# H_bridge.net
KiCad netlist of a schematic drawn in Altium Designer
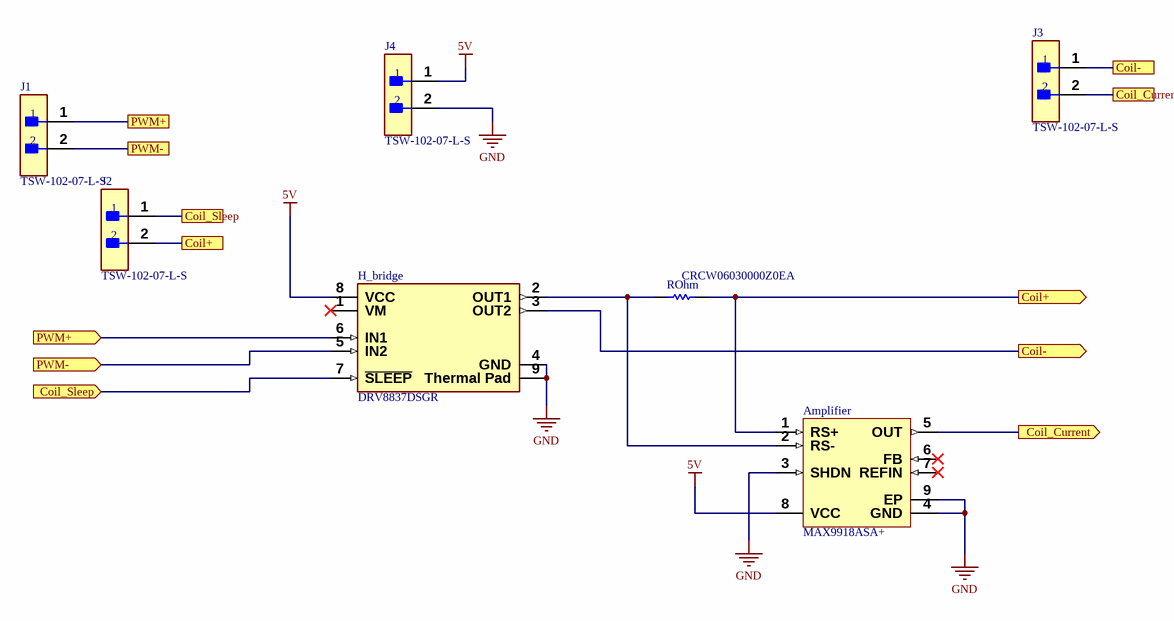
[diagram p0: H_bridge.SchDoc]

(export (version "E")
  (design (tool "Eeschema 10.0.6"))
  (components
    (comp (ref "Amplifier")
      (value "MAX9918ASA+")
      (footprint "MAXM-S8E+14_L")
      (libsource (lib "Altium Content Vault") (part "MAX99XX-S8E+14"))
    )
    (comp (ref "H_bridge")
      (value "DRV8837DSGR")
      (footprint "FP-DSG0008A-MFG")
      (description "IC MOTOR DRIVER PAR 8WSON")
      (fields
        (field (name "MANUFACTURER") "Texas Instruments")
        (field (name "OCTOPART") "https://octopart.com/drv8837dsgr-texas+instruments-23786726")
      )
      (libsource (lib "Altium Content Vault") (part "0edabe62f55b79d65ef7cb8a22a7164"))
    )
    (comp (ref "J1")
      (value "TSW-102-07-L-S")
      (footprint "FP-TSW-102-07-L-S-MFG")
      (description "CONN HEADER VERT 2POS 2.54MM")
      (libsource (lib "Altium Content Vault") (part "3bc925449376181038e59eaffc5286c"))
    )
    (comp (ref "J2")
      (value "TSW-102-07-L-S")
      (footprint "FP-TSW-102-07-L-S-MFG")
      (description "CONN HEADER VERT 2POS 2.54MM")
      (libsource (lib "Altium Content Vault") (part "3bc925449376181038e59eaffc5286c"))
    )
    (comp (ref "J3")
      (value "TSW-102-07-L-S")
      (footprint "FP-TSW-102-07-L-S-MFG")
      (description "CONN HEADER VERT 2POS 2.54MM")
      (libsource (lib "Altium Content Vault") (part "3bc925449376181038e59eaffc5286c"))
    )
    (comp (ref "J4")
      (value "TSW-102-07-L-S")
      (footprint "FP-TSW-102-07-L-S-MFG")
      (description "CONN HEADER VERT 2POS 2.54MM")
      (libsource (lib "Altium Content Vault") (part "3bc925449376181038e59eaffc5286c"))
    )
    (comp (ref "ROhm")
      (value "CRCW06030000Z0EA")
      (footprint "RESC1609X50X30NL8T20")
      (description "Chip Resistor, 0 Ohm, Jumper, 100 mW, -55 to 155 degC, 0603 (1608 Metric), RoHS, Tape and Reel")
      (fields (field (name "MANUFACTURER") "Vishay Semiconductor"))
      (libsource (lib "Altium Content Vault") (part "RES-2"))
    )
  )
  (nets
    (net (code "1") (name "/Coil+") (class "Default")
      (node (ref "Amplifier") (pin "1") (pinfunction "RS+_1") (pintype "input"))
      (node (ref "J2") (pin "2") (pinfunction "2_2") (pintype "passive"))
      (node (ref "ROhm") (pin "2") (pinfunction "2_2") (pintype "passive"))
    )
    (net (code "2") (name "/Coil-") (class "Default")
      (node (ref "H_bridge") (pin "3") (pinfunction "OUT2_3") (pintype "output"))
      (node (ref "J3") (pin "1") (pinfunction "1_1") (pintype "passive"))
    )
    (net (code "3") (name "/Coil_Current") (class "Default")
      (node (ref "Amplifier") (pin "5") (pinfunction "OUT_5") (pintype "output"))
      (node (ref "J3") (pin "2") (pinfunction "2_2") (pintype "passive"))
    )
    (net (code "4") (name "/Coil_Sleep") (class "Default")
      (node (ref "H_bridge") (pin "7") (pinfunction "~{SLEEP}_7") (pintype "input"))
      (node (ref "J2") (pin "1") (pinfunction "1_1") (pintype "passive"))
    )
    (net (code "5") (name "/PWM+") (class "Default")
      (node (ref "H_bridge") (pin "6") (pinfunction "IN1_6") (pintype "input"))
      (node (ref "J1") (pin "1") (pinfunction "1_1") (pintype "passive"))
    )
    (net (code "6") (name "/PWM-") (class "Default")
      (node (ref "H_bridge") (pin "5") (pinfunction "IN2_5") (pintype "input"))
      (node (ref "J1") (pin "2") (pinfunction "2_2") (pintype "passive"))
    )
    (net (code "7") (name "5V") (class "Default")
      (node (ref "Amplifier") (pin "8") (pinfunction "VCC_8") (pintype "power_in"))
      (node (ref "H_bridge") (pin "8") (pinfunction "VCC_8") (pintype "power_in"))
      (node (ref "J4") (pin "1") (pinfunction "1_1") (pintype "passive"))
    )
    (net (code "8") (name "GND") (class "Default")
      (node (ref "Amplifier") (pin "3") (pinfunction "SHDN_3") (pintype "input"))
      (node (ref "Amplifier") (pin "4") (pinfunction "GND_4") (pintype "power_in"))
      (node (ref "Amplifier") (pin "9") (pinfunction "EP_9") (pintype "power_in"))
      (node (ref "H_bridge") (pin "4") (pinfunction "GND_4") (pintype "power_in"))
      (node (ref "H_bridge") (pin "9") (pinfunction "Thermal_Pad_9") (pintype "power_in"))
      (node (ref "J4") (pin "2") (pinfunction "2_2") (pintype "passive"))
    )
    (net (code "9") (name "Net-(Amplifier-RS-)") (class "Default")
      (node (ref "Amplifier") (pin "2") (pinfunction "RS-_2") (pintype "input"))
      (node (ref "H_bridge") (pin "2") (pinfunction "OUT1_2") (pintype "output"))
      (node (ref "ROhm") (pin "1") (pinfunction "1_1") (pintype "passive"))
    )
    (net (code "10") (name "unconnected-(Amplifier-FB-Pad6)") (class "Default")
      (node (ref "Amplifier") (pin "6") (pinfunction "FB_6") (pintype "input+no_connect"))
    )
    (net (code "11") (name "unconnected-(Amplifier-REFIN-Pad7)") (class "Default")
      (node (ref "Amplifier") (pin "7") (pinfunction "REFIN_7") (pintype "input+no_connect"))
    )
    (net (code "12") (name "unconnected-(H_bridge-VM-Pad1)") (class "Default")
      (node (ref "H_bridge") (pin "1") (pinfunction "VM_1") (pintype "power_in+no_connect"))
    )
  )
)
